# Power.net
KiCad netlist of a schematic drawn in Altium Designer
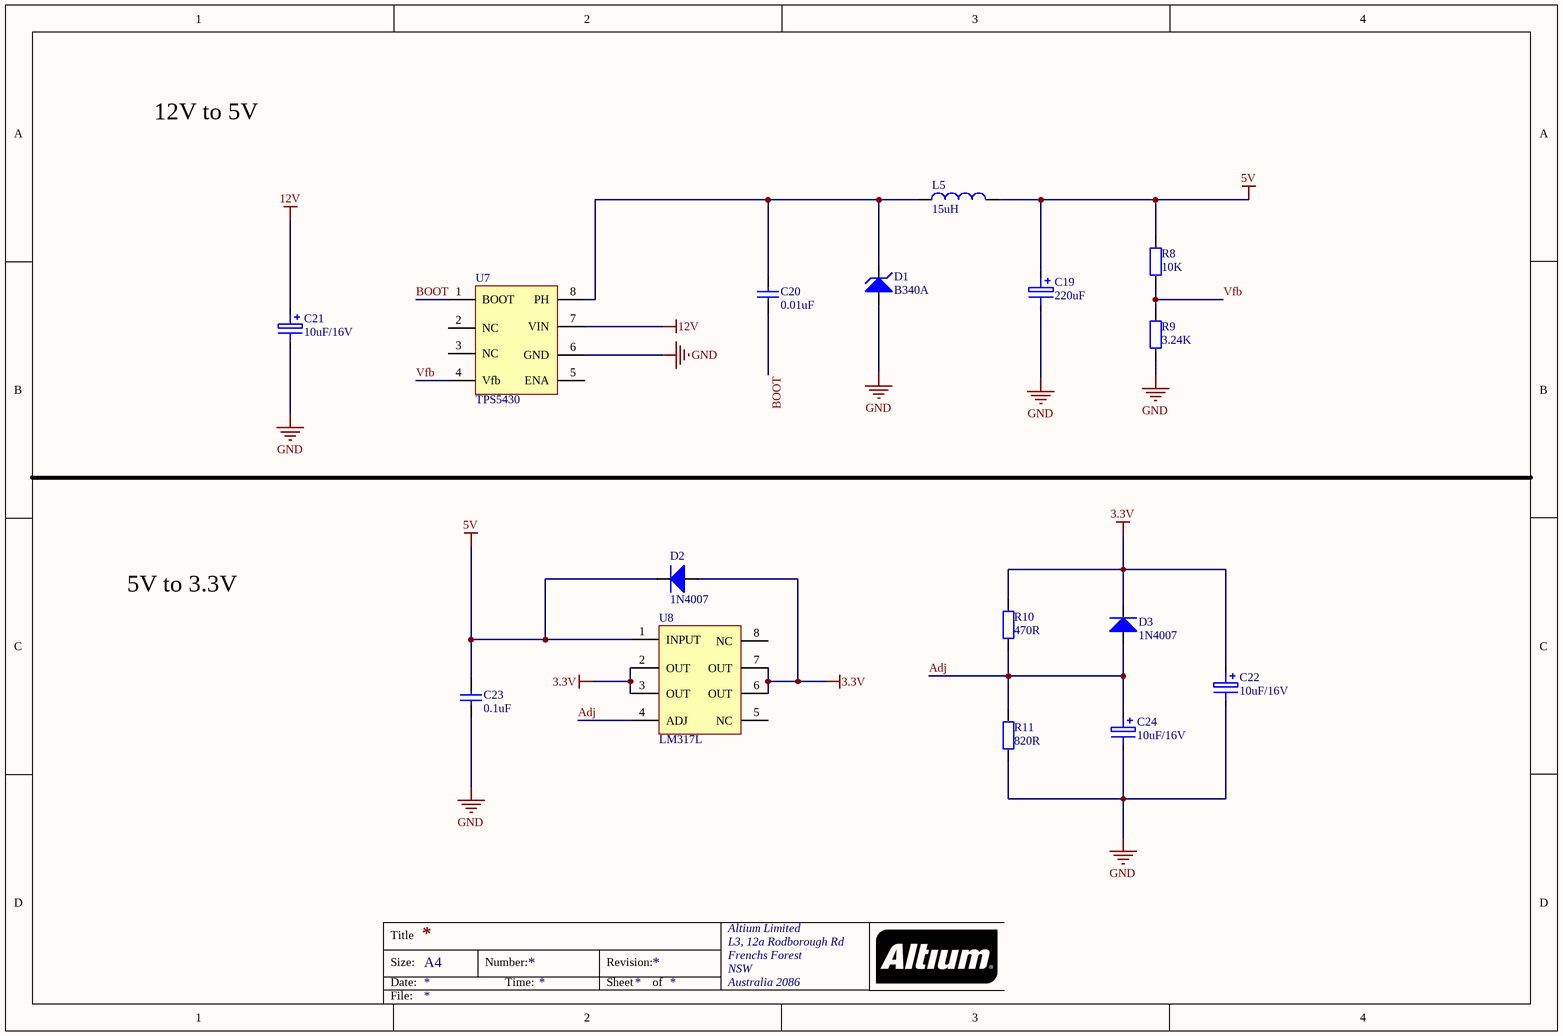
[diagram p0: Power.SchDoc]

(export (version "E")
  (design (tool "Eeschema 10.0.6"))
  (components
    (comp (ref "C19")
      (value "220uF")
      (footprint "CAPM-7.0*4.5")
      (description "aluminum")
      (libsource (lib "ToponLib") (part "Cap3"))
    )
    (comp (ref "C20")
      (value "0.01uF")
      (footprint "0603")
      (description "ceramic")
      (libsource (lib "ToponLib") (part "Cap1"))
    )
    (comp (ref "C21")
      (value "10uF/16V")
      (footprint "CAPM-7.0*4.5")
      (description "aluminum")
      (libsource (lib "ToponLib") (part "Cap3"))
    )
    (comp (ref "C22")
      (value "10uF/16V")
      (footprint "CAPM-5.5*3.3")
      (description "aluminum")
      (libsource (lib "ToponLib") (part "Cap3"))
    )
    (comp (ref "C23")
      (value "0.1uF")
      (footprint "0603")
      (description "ceramic")
      (libsource (lib "ToponLib") (part "Cap1"))
    )
    (comp (ref "C24")
      (value "10uF/16V")
      (footprint "CAPM-5.5*3.3")
      (description "aluminum")
      (libsource (lib "ToponLib") (part "Cap3"))
    )
    (comp (ref "D1") (value "B340A") (footprint "DO214-AC") (libsource (lib "ToponLib") (part "B340A-13-F")))
    (comp (ref "D2") (value "1N4007") (footprint "DO214-AC") (libsource (lib "ToponLib") (part "1N4007")))
    (comp (ref "D3") (value "1N4007") (footprint "DO214-AC") (libsource (lib "ToponLib") (part "1N4007")))
    (comp (ref "L5") (value "15uH") (footprint "7*7*4-15uH") (libsource (lib "ToponLib") (part "Inductor")))
    (comp (ref "R8") (value "10K") (footprint "0603") (libsource (lib "ToponLib") (part "Res")))
    (comp (ref "R9") (value "3.24K") (footprint "0603") (libsource (lib "ToponLib") (part "Res")))
    (comp (ref "R10") (value "470R") (footprint "0603") (libsource (lib "ToponLib") (part "Res")))
    (comp (ref "R11") (value "820R") (footprint "0603") (libsource (lib "ToponLib") (part "Res")))
    (comp (ref "U7") (value "TPS5430") (footprint "TPS5430") (libsource (lib "ToponLib") (part "TPS5430")))
    (comp (ref "U8") (value "LM317L") (footprint "LM317L") (libsource (lib "ToponLib") (part "LM317L")))
  )
  (nets
    (net (code "1") (name "/Adj") (class "Default")
      (node (ref "C24") (pin "1") (pinfunction "1_1") (pintype "passive"))
      (node (ref "D3") (pin "1") (pinfunction "A_1") (pintype "passive"))
      (node (ref "R10") (pin "1") (pinfunction "1_1") (pintype "passive"))
      (node (ref "R11") (pin "2") (pinfunction "2_2") (pintype "passive"))
      (node (ref "U8") (pin "4") (pinfunction "ADJ_4") (pintype "passive"))
    )
    (net (code "2") (name "/BOOT") (class "Default")
      (node (ref "C20") (pin "1") (pinfunction "1_1") (pintype "passive"))
      (node (ref "U7") (pin "1") (pinfunction "BOOT_1") (pintype "passive"))
    )
    (net (code "3") (name "/Vfb") (class "Default")
      (node (ref "R8") (pin "1") (pinfunction "1_1") (pintype "passive"))
      (node (ref "R9") (pin "2") (pinfunction "2_2") (pintype "passive"))
      (node (ref "U7") (pin "4") (pinfunction "Vfb_4") (pintype "passive"))
    )
    (net (code "4") (name "3.3V") (class "Default")
      (node (ref "C22") (pin "1") (pinfunction "1_1") (pintype "passive"))
      (node (ref "D2") (pin "1") (pinfunction "A_1") (pintype "passive"))
      (node (ref "D3") (pin "2") (pinfunction "K_2") (pintype "passive"))
      (node (ref "R10") (pin "2") (pinfunction "2_2") (pintype "passive"))
      (node (ref "U8") (pin "2") (pinfunction "OUT_2") (pintype "passive"))
      (node (ref "U8") (pin "3") (pinfunction "OUT_3") (pintype "passive"))
      (node (ref "U8") (pin "6") (pinfunction "OUT_6") (pintype "passive"))
      (node (ref "U8") (pin "7") (pinfunction "OUT_7") (pintype "passive"))
    )
    (net (code "5") (name "5V") (class "Default")
      (node (ref "C19") (pin "1") (pinfunction "1_1") (pintype "passive"))
      (node (ref "C23") (pin "2") (pinfunction "2_2") (pintype "passive"))
      (node (ref "D2") (pin "2") (pinfunction "K_2") (pintype "passive"))
      (node (ref "L5") (pin "2") (pinfunction "2_2") (pintype "passive"))
      (node (ref "R8") (pin "2") (pinfunction "2_2") (pintype "passive"))
      (node (ref "U8") (pin "1") (pinfunction "INPUT_1") (pintype "passive"))
    )
    (net (code "6") (name "12V") (class "Default")
      (node (ref "C21") (pin "1") (pinfunction "1_1") (pintype "passive"))
      (node (ref "U7") (pin "7") (pinfunction "VIN_7") (pintype "passive"))
    )
    (net (code "7") (name "GND") (class "Default")
      (node (ref "C19") (pin "2") (pinfunction "2_2") (pintype "passive"))
      (node (ref "C21") (pin "2") (pinfunction "2_2") (pintype "passive"))
      (node (ref "C22") (pin "2") (pinfunction "2_2") (pintype "passive"))
      (node (ref "C23") (pin "1") (pinfunction "1_1") (pintype "passive"))
      (node (ref "C24") (pin "2") (pinfunction "2_2") (pintype "passive"))
      (node (ref "D1") (pin "1") (pinfunction "A_1") (pintype "passive"))
      (node (ref "R11") (pin "1") (pinfunction "1_1") (pintype "passive"))
      (node (ref "R9") (pin "1") (pinfunction "1_1") (pintype "passive"))
      (node (ref "U7") (pin "6") (pinfunction "GND_6") (pintype "passive"))
    )
    (net (code "8") (name "Net-(D1-K)") (class "Default")
      (node (ref "C20") (pin "2") (pinfunction "2_2") (pintype "passive"))
      (node (ref "D1") (pin "2") (pinfunction "K_2") (pintype "passive"))
      (node (ref "L5") (pin "1") (pinfunction "1_1") (pintype "passive"))
      (node (ref "U7") (pin "8") (pinfunction "PH_8") (pintype "passive"))
    )
    (net (code "9") (name "unconnected-(U7-ENA-Pad5)") (class "Default")
      (node (ref "U7") (pin "5") (pinfunction "ENA_5") (pintype "passive"))
    )
    (net (code "10") (name "unconnected-(U7-NC-Pad2)") (class "Default")
      (node (ref "U7") (pin "2") (pinfunction "NC_2") (pintype "passive"))
    )
    (net (code "11") (name "unconnected-(U7-NC-Pad3)") (class "Default")
      (node (ref "U7") (pin "3") (pinfunction "NC_3") (pintype "passive"))
    )
    (net (code "12") (name "unconnected-(U8-NC-Pad5)") (class "Default")
      (node (ref "U8") (pin "5") (pinfunction "NC_5") (pintype "passive"))
    )
    (net (code "13") (name "unconnected-(U8-NC-Pad8)") (class "Default")
      (node (ref "U8") (pin "8") (pinfunction "NC_8") (pintype "passive"))
    )
  )
)
